# USB.net
KiCad netlist of a schematic drawn in Altium Designer
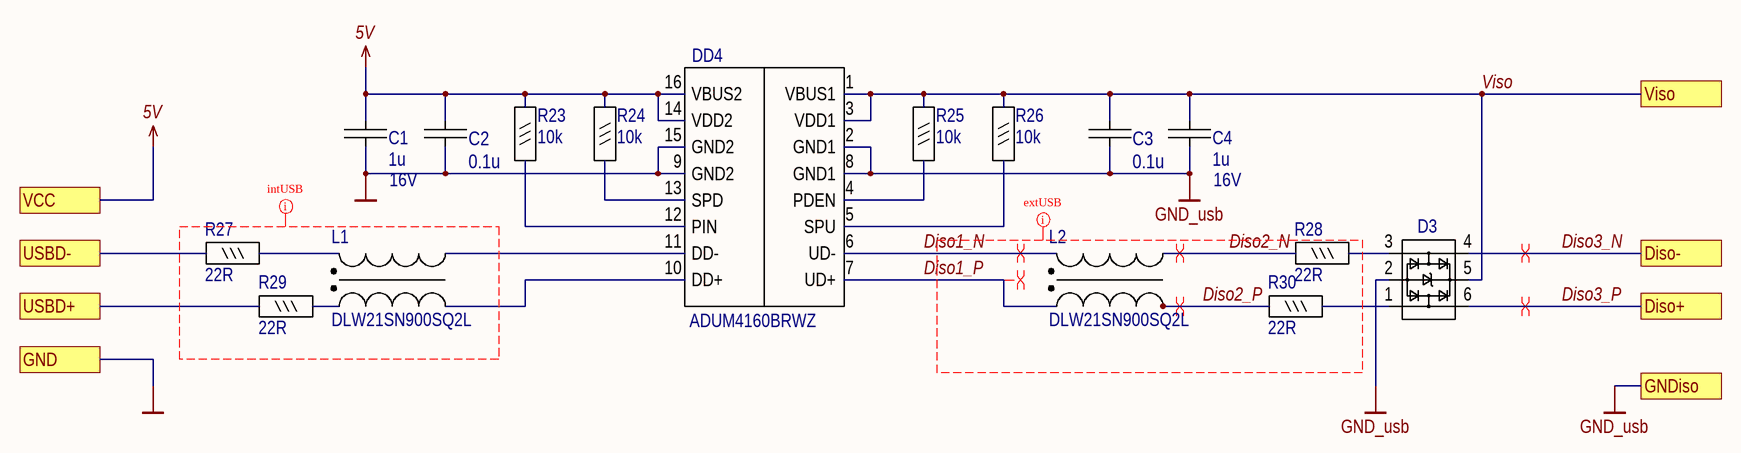
[diagram p0: USB.SchDoc]

(export (version "E")
  (design (tool "Eeschema 10.0.6"))
  (components
    (comp (ref "C1")
      (value "1u")
      (footprint "C0603_IPC")
      (description "1µF ±10% 16V Ceramic Capacitor X7R 0603 (1608 Metric)")
      (fields
        (field (name "MPN") "CC0603KRX7R7BB105")
        (field (name "TOLERANCE") "0,1")
        (field (name "VOLTAGE/POWER") "16V")
      )
      (libsource (lib "DB_res_cap_ind") (part "C0603_GOST"))
    )
    (comp (ref "C2")
      (value "0.1u")
      (footprint "C0603_IPC")
      (description "0.1uF ±10% 50V Ceramic Capacitor X7R 0603 (1608 Metric)")
      (fields (field (name "PARTNUMBER") "0.1u 50V") (field (name "MPN") "CL10B104KB8NNND"))
      (libsource (lib "DB_res_cap_ind") (part "C0603_GOST"))
    )
    (comp (ref "C3")
      (value "0.1u")
      (footprint "C0603_IPC")
      (description "0.1uF ±10% 50V Ceramic Capacitor X7R 0603 (1608 Metric)")
      (fields (field (name "PARTNUMBER") "0.1u 50V") (field (name "MPN") "CL10B104KB8NNND"))
      (libsource (lib "DB_res_cap_ind") (part "C0603_GOST"))
    )
    (comp (ref "C4")
      (value "1u")
      (footprint "C0603_IPC")
      (description "1µF ±10% 16V Ceramic Capacitor X7R 0603 (1608 Metric)")
      (fields
        (field (name "MPN") "CC0603KRX7R7BB105")
        (field (name "TOLERANCE") "0,1")
        (field (name "VOLTAGE/POWER") "16V")
      )
      (libsource (lib "DB_res_cap_ind") (part "C0603_GOST"))
    )
    (comp (ref "D3")
      (value "USBLC6-2SC6")
      (footprint "sot23-6")
      (description "TVS DIODE 5.25V 17V SOT23-6")
      (libsource (lib "DB_the_rest") (part "USBLC6-2SC6"))
    )
    (comp (ref "DD4")
      (value "ADUM4160BRWZ")
      (footprint "SOIC16W")
      (description "Digital isolator; 3.1Г·5.5VDC; Interface: USB; SMD; SO16")
      (libsource (lib "IC") (part "ADUM4160BRWZ"))
    )
    (comp (ref "L1")
      (value "DLW21SN900SQ2L")
      (footprint "DLW21S 0805")
      (description "CMC 330MA 2LN 90 OHM SMD")
      (libsource (lib "DB_res_cap_ind") (part "DLW21SN_SQ"))
    )
    (comp (ref "L2")
      (value "DLW21SN900SQ2L")
      (footprint "DLW21S 0805")
      (description "CMC 330MA 2LN 90 OHM SMD")
      (libsource (lib "DB_res_cap_ind") (part "DLW21SN_SQ"))
    )
    (comp (ref "R23")
      (value "10k")
      (footprint "R0603")
      (description "10 kOhms ±5% 0.1W, 1/10W Chip Resistor 0603 (1608 Metric) Moisture Resistant Thick Film")
      (fields (field (name "MPN") "RC0603JR-0710kL") (field (name "TOLERANCE") "5%"))
      (libsource (lib "DB_res_cap_ind") (part "R0603"))
    )
    (comp (ref "R24")
      (value "10k")
      (footprint "R0603")
      (description "10 kOhms ±5% 0.1W, 1/10W Chip Resistor 0603 (1608 Metric) Moisture Resistant Thick Film")
      (fields (field (name "MPN") "RC0603JR-0710kL") (field (name "TOLERANCE") "5%"))
      (libsource (lib "DB_res_cap_ind") (part "R0603"))
    )
    (comp (ref "R25")
      (value "10k")
      (footprint "R0603")
      (description "10 kOhms ±5% 0.1W, 1/10W Chip Resistor 0603 (1608 Metric) Moisture Resistant Thick Film")
      (fields (field (name "MPN") "RC0603JR-0710kL") (field (name "TOLERANCE") "5%"))
      (libsource (lib "DB_res_cap_ind") (part "R0603"))
    )
    (comp (ref "R26")
      (value "10k")
      (footprint "R0603")
      (description "10 kOhms ±5% 0.1W, 1/10W Chip Resistor 0603 (1608 Metric) Moisture Resistant Thick Film")
      (fields (field (name "MPN") "RC0603JR-0710kL") (field (name "TOLERANCE") "5%"))
      (libsource (lib "DB_res_cap_ind") (part "R0603"))
    )
    (comp (ref "R27")
      (value "22R")
      (footprint "R0603")
      (description "22 Ohms ±5% 0.1W, 1/10W Chip Resistor 0603 (1608 Metric) Moisture Resistant Thick Film")
      (fields (field (name "MPN") "RC0603JR-0722RL") (field (name "TOLERANCE") "5%"))
      (libsource (lib "DB_res_cap_ind") (part "R0603"))
    )
    (comp (ref "R28")
      (value "22R")
      (footprint "R0603")
      (description "22 Ohms ±5% 0.1W, 1/10W Chip Resistor 0603 (1608 Metric) Moisture Resistant Thick Film")
      (fields (field (name "MPN") "RC0603JR-0722RL") (field (name "TOLERANCE") "5%"))
      (libsource (lib "DB_res_cap_ind") (part "R0603"))
    )
    (comp (ref "R29")
      (value "22R")
      (footprint "R0603")
      (description "22 Ohms ±5% 0.1W, 1/10W Chip Resistor 0603 (1608 Metric) Moisture Resistant Thick Film")
      (fields (field (name "MPN") "RC0603JR-0722RL") (field (name "TOLERANCE") "5%"))
      (libsource (lib "DB_res_cap_ind") (part "R0603"))
    )
    (comp (ref "R30")
      (value "22R")
      (footprint "R0603")
      (description "22 Ohms ±5% 0.1W, 1/10W Chip Resistor 0603 (1608 Metric) Moisture Resistant Thick Film")
      (fields (field (name "MPN") "RC0603JR-0722RL") (field (name "TOLERANCE") "5%"))
      (libsource (lib "DB_res_cap_ind") (part "R0603"))
    )
  )
  (nets
    (net (code "1") (name "/Diso1_N") (class "Default")
      (node (ref "DD4") (pin "6") (pinfunction "UD-_6") (pintype "passive"))
      (node (ref "L2") (pin "1") (pinfunction "1_1") (pintype "passive"))
    )
    (net (code "2") (name "/Diso1_P") (class "Default")
      (node (ref "DD4") (pin "7") (pinfunction "UD+_7") (pintype "passive"))
      (node (ref "L2") (pin "4") (pinfunction "4_4") (pintype "passive"))
    )
    (net (code "3") (name "/Diso2_N") (class "Default")
      (node (ref "L2") (pin "2") (pinfunction "2_2") (pintype "passive"))
      (node (ref "R28") (pin "1") (pinfunction "1_1") (pintype "passive"))
    )
    (net (code "4") (name "/Diso2_P") (class "Default")
      (node (ref "L2") (pin "3") (pinfunction "3_3") (pintype "passive"))
      (node (ref "R30") (pin "1") (pinfunction "1_1") (pintype "passive"))
    )
    (net (code "5") (name "/Diso3_N") (class "Default")
      (node (ref "D3") (pin "4") (pinfunction "IO2_4") (pintype "power_in"))
    )
    (net (code "6") (name "/Diso3_P") (class "Default")
      (node (ref "D3") (pin "6") (pinfunction "IO1_6") (pintype "power_in"))
    )
    (net (code "7") (name "/USBD+") (class "Default")
      (node (ref "R29") (pin "1") (pinfunction "1_1") (pintype "passive"))
    )
    (net (code "8") (name "/USBD-") (class "Default")
      (node (ref "R27") (pin "1") (pinfunction "1_1") (pintype "passive"))
    )
    (net (code "9") (name "/Viso") (class "Default")
      (node (ref "C3") (pin "1") (pinfunction "1_1") (pintype "passive"))
      (node (ref "C4") (pin "1") (pinfunction "1_1") (pintype "passive"))
      (node (ref "D3") (pin "5") (pinfunction "Vbus_5") (pintype "power_in"))
      (node (ref "DD4") (pin "1") (pinfunction "VBUS1_1") (pintype "passive"))
      (node (ref "DD4") (pin "3") (pinfunction "VDD1_3") (pintype "passive"))
      (node (ref "R25") (pin "2") (pinfunction "2_2") (pintype "passive"))
      (node (ref "R26") (pin "2") (pinfunction "2_2") (pintype "passive"))
    )
    (net (code "10") (name "5V") (class "Default")
      (node (ref "C1") (pin "1") (pinfunction "1_1") (pintype "passive"))
      (node (ref "C2") (pin "1") (pinfunction "1_1") (pintype "passive"))
      (node (ref "DD4") (pin "14") (pinfunction "VDD2_14") (pintype "passive"))
      (node (ref "DD4") (pin "16") (pinfunction "VBUS2_16") (pintype "passive"))
      (node (ref "R23") (pin "2") (pinfunction "2_2") (pintype "passive"))
      (node (ref "R24") (pin "2") (pinfunction "2_2") (pintype "passive"))
    )
    (net (code "11") (name "GND") (class "Default")
      (node (ref "C1") (pin "2") (pinfunction "2_2") (pintype "passive"))
      (node (ref "C2") (pin "2") (pinfunction "2_2") (pintype "passive"))
      (node (ref "DD4") (pin "15") (pinfunction "GND2_15") (pintype "passive"))
      (node (ref "DD4") (pin "9") (pinfunction "GND2_9") (pintype "passive"))
    )
    (net (code "12") (name "GND_usb") (class "Default")
      (node (ref "C3") (pin "2") (pinfunction "2_2") (pintype "passive"))
      (node (ref "C4") (pin "2") (pinfunction "2_2") (pintype "passive"))
      (node (ref "D3") (pin "2") (pinfunction "GND_2") (pintype "power_in"))
      (node (ref "DD4") (pin "2") (pinfunction "GND1_2") (pintype "passive"))
      (node (ref "DD4") (pin "8") (pinfunction "GND1_8") (pintype "passive"))
    )
    (net (code "13") (name "Net-(D3-IO1-Pad1)") (class "Default")
      (node (ref "D3") (pin "1") (pinfunction "IO1_1") (pintype "power_in"))
      (node (ref "R30") (pin "2") (pinfunction "2_2") (pintype "passive"))
    )
    (net (code "14") (name "Net-(D3-IO2-Pad3)") (class "Default")
      (node (ref "D3") (pin "3") (pinfunction "IO2_3") (pintype "power_in"))
      (node (ref "R28") (pin "2") (pinfunction "2_2") (pintype "passive"))
    )
    (net (code "15") (name "Net-(DD4-DD+)") (class "Default")
      (node (ref "DD4") (pin "10") (pinfunction "DD+_10") (pintype "passive"))
      (node (ref "L1") (pin "3") (pinfunction "3_3") (pintype "passive"))
    )
    (net (code "16") (name "Net-(DD4-DD-)") (class "Default")
      (node (ref "DD4") (pin "11") (pinfunction "DD-_11") (pintype "passive"))
      (node (ref "L1") (pin "2") (pinfunction "2_2") (pintype "passive"))
    )
    (net (code "17") (name "Net-(DD4-PDEN)") (class "Default")
      (node (ref "DD4") (pin "4") (pinfunction "PDEN_4") (pintype "passive"))
      (node (ref "R25") (pin "1") (pinfunction "1_1") (pintype "passive"))
    )
    (net (code "18") (name "Net-(DD4-PIN)") (class "Default")
      (node (ref "DD4") (pin "12") (pinfunction "PIN_12") (pintype "passive"))
      (node (ref "R23") (pin "1") (pinfunction "1_1") (pintype "passive"))
    )
    (net (code "19") (name "Net-(DD4-SPD)") (class "Default")
      (node (ref "DD4") (pin "13") (pinfunction "SPD_13") (pintype "passive"))
      (node (ref "R24") (pin "1") (pinfunction "1_1") (pintype "passive"))
    )
    (net (code "20") (name "Net-(DD4-SPU)") (class "Default")
      (node (ref "DD4") (pin "5") (pinfunction "SPU_5") (pintype "passive"))
      (node (ref "R26") (pin "1") (pinfunction "1_1") (pintype "passive"))
    )
    (net (code "21") (name "Net-(L1-Pad1)") (class "Default")
      (node (ref "L1") (pin "1") (pinfunction "1_1") (pintype "passive"))
      (node (ref "R27") (pin "2") (pinfunction "2_2") (pintype "passive"))
    )
    (net (code "22") (name "Net-(L1-Pad4)") (class "Default")
      (node (ref "L1") (pin "4") (pinfunction "4_4") (pintype "passive"))
      (node (ref "R29") (pin "2") (pinfunction "2_2") (pintype "passive"))
    )
  )
)
